# Moror_Driver_and_Power_Board_v2.net
KiCad netlist of a schematic drawn in EAGLE
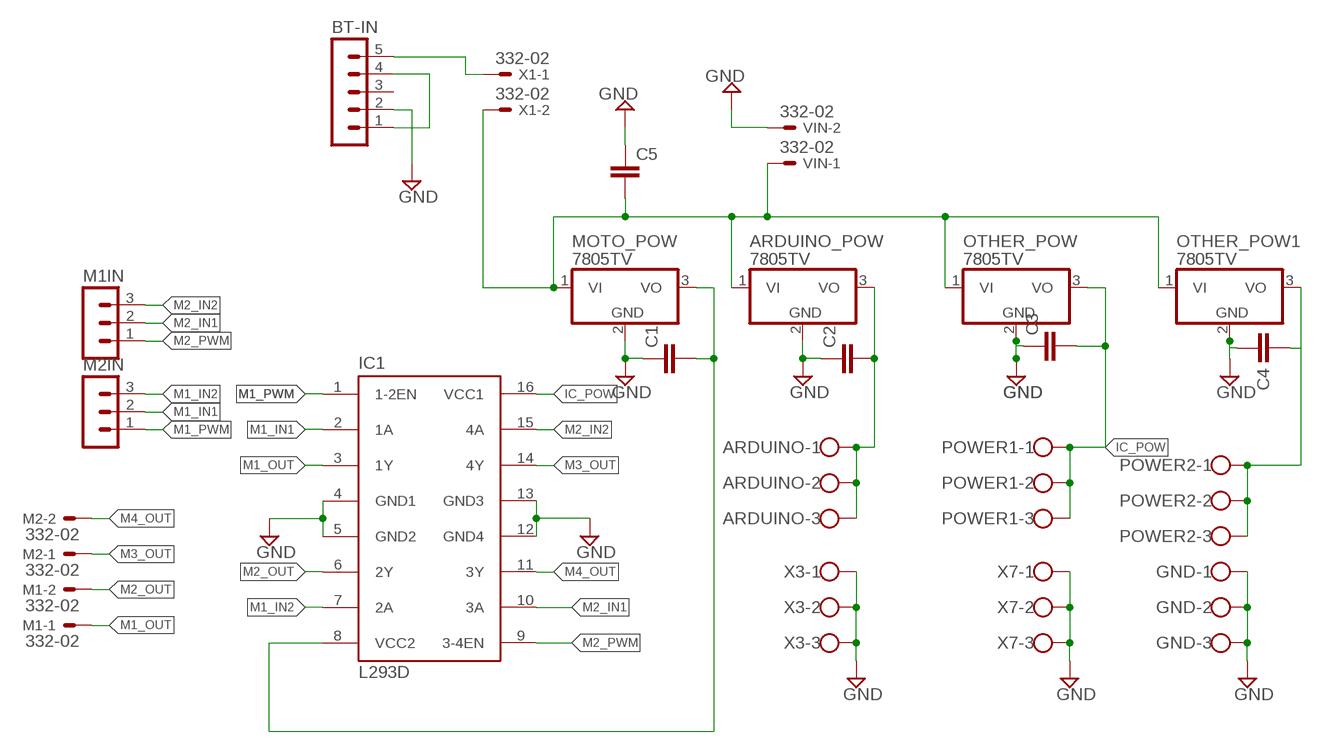
[diagram p0: schematic, sheet 1]

(export (version "E")
  (design (tool "Eeschema 10.0.6"))
  (components
    (comp (ref "ARDUINO")
      (value "W237-103")
      (footprint "eagle-import:W237-103")
      (fields (field (name "MPN") "237-103"))
      (libsource (lib "eagle-import") (part "W237-103"))
    )
    (comp (ref "ARDUINO_POW")
      (value "7805TV")
      (footprint "eagle-import:TO220V")
      (libsource (lib "eagle-import") (part "78TV05"))
    )
    (comp (ref "BT-IN")
      (value "MA05-1")
      (footprint "eagle-import:MA05-1")
      (libsource (lib "eagle-import") (part "MA05-1"))
    )
    (comp (ref "C1")
      (value "C-EU025-030X050")
      (footprint "eagle-import:C025-030X050")
      (libsource (lib "eagle-import") (part "C-EU025-030X050"))
    )
    (comp (ref "C2")
      (value "C-EU025-030X050")
      (footprint "eagle-import:C025-030X050")
      (libsource (lib "eagle-import") (part "C-EU025-030X050"))
    )
    (comp (ref "C3")
      (value "C-EU025-030X050")
      (footprint "eagle-import:C025-030X050")
      (libsource (lib "eagle-import") (part "C-EU025-030X050"))
    )
    (comp (ref "C4")
      (value "C-EU025-030X050")
      (footprint "eagle-import:C025-030X050")
      (libsource (lib "eagle-import") (part "C-EU025-030X050"))
    )
    (comp (ref "C5")
      (value "C-EU025-030X050")
      (footprint "eagle-import:C025-030X050")
      (libsource (lib "eagle-import") (part "C-EU025-030X050"))
    )
    (comp (ref "GND")
      (value "W237-103")
      (footprint "eagle-import:W237-103")
      (fields (field (name "MPN") "237-103"))
      (libsource (lib "eagle-import") (part "W237-103"))
    )
    (comp (ref "IC1")
      (value "L293D")
      (footprint "eagle-import:DIL16")
      (libsource (lib "eagle-import") (part "L293D"))
    )
    (comp (ref "M1")
      (value "332-02")
      (footprint "eagle-import:332-02")
      (libsource (lib "eagle-import") (part "332-02"))
    )
    (comp (ref "M1IN")
      (value "MA03-1")
      (footprint "eagle-import:MA03-1")
      (libsource (lib "eagle-import") (part "MA03-1"))
    )
    (comp (ref "M2")
      (value "332-02")
      (footprint "eagle-import:332-02")
      (libsource (lib "eagle-import") (part "332-02"))
    )
    (comp (ref "M2IN")
      (value "MA03-1")
      (footprint "eagle-import:MA03-1")
      (libsource (lib "eagle-import") (part "MA03-1"))
    )
    (comp (ref "MOTO_POW")
      (value "7805TV")
      (footprint "eagle-import:TO220V")
      (libsource (lib "eagle-import") (part "78TV05"))
    )
    (comp (ref "OTHER_POW")
      (value "7805TV")
      (footprint "eagle-import:TO220V")
      (libsource (lib "eagle-import") (part "78TV05"))
    )
    (comp (ref "OTHER_POW1")
      (value "7805TV")
      (footprint "eagle-import:TO220V")
      (libsource (lib "eagle-import") (part "78TV05"))
    )
    (comp (ref "POWER1")
      (value "W237-103")
      (footprint "eagle-import:W237-103")
      (fields (field (name "MPN") "237-103"))
      (libsource (lib "eagle-import") (part "W237-103"))
    )
    (comp (ref "POWER2")
      (value "W237-103")
      (footprint "eagle-import:W237-103")
      (fields (field (name "MPN") "237-103"))
      (libsource (lib "eagle-import") (part "W237-103"))
    )
    (comp (ref "VIN")
      (value "332-02")
      (footprint "eagle-import:332-02")
      (libsource (lib "eagle-import") (part "332-02"))
    )
    (comp (ref "X1")
      (value "332-02")
      (footprint "eagle-import:332-02")
      (libsource (lib "eagle-import") (part "332-02"))
    )
    (comp (ref "X3")
      (value "W237-103")
      (footprint "eagle-import:W237-103")
      (fields (field (name "MPN") "237-103"))
      (libsource (lib "eagle-import") (part "W237-103"))
    )
    (comp (ref "X7")
      (value "W237-103")
      (footprint "eagle-import:W237-103")
      (fields (field (name "MPN") "237-103"))
      (libsource (lib "eagle-import") (part "W237-103"))
    )
  )
  (nets
    (net (code "1") (name "GND") (class "Default")
      (node (ref "ARDUINO_POW") (pin "2") (pinfunction "GND_2") (pintype "passive"))
      (node (ref "BT-IN") (pin "2") (pinfunction "2_2") (pintype "passive"))
      (node (ref "C1") (pin "1") (pinfunction "1_1") (pintype "passive"))
      (node (ref "C2") (pin "1") (pinfunction "1_1") (pintype "passive"))
      (node (ref "C3") (pin "1") (pinfunction "1_1") (pintype "passive"))
      (node (ref "C4") (pin "1") (pinfunction "1_1") (pintype "passive"))
      (node (ref "C5") (pin "1") (pinfunction "1_1") (pintype "passive"))
      (node (ref "GND") (pin "1") (pinfunction "KL_1") (pintype "passive"))
      (node (ref "GND") (pin "2") (pinfunction "KL_2") (pintype "passive"))
      (node (ref "GND") (pin "3") (pinfunction "KL_3") (pintype "passive"))
      (node (ref "IC1") (pin "12") (pinfunction "GND4_12") (pintype "power_in"))
      (node (ref "IC1") (pin "13") (pinfunction "GND3_13") (pintype "power_in"))
      (node (ref "IC1") (pin "4") (pinfunction "GND1_4") (pintype "power_in"))
      (node (ref "IC1") (pin "5") (pinfunction "GND2_5") (pintype "power_in"))
      (node (ref "MOTO_POW") (pin "2") (pinfunction "GND_2") (pintype "passive"))
      (node (ref "OTHER_POW") (pin "2") (pinfunction "GND_2") (pintype "passive"))
      (node (ref "OTHER_POW1") (pin "2") (pinfunction "GND_2") (pintype "passive"))
      (node (ref "VIN") (pin "2") (pinfunction "S_2") (pintype "passive"))
      (node (ref "X3") (pin "1") (pinfunction "KL_1") (pintype "passive"))
      (node (ref "X3") (pin "2") (pinfunction "KL_2") (pintype "passive"))
      (node (ref "X3") (pin "3") (pinfunction "KL_3") (pintype "passive"))
      (node (ref "X7") (pin "1") (pinfunction "KL_1") (pintype "passive"))
      (node (ref "X7") (pin "2") (pinfunction "KL_2") (pintype "passive"))
      (node (ref "X7") (pin "3") (pinfunction "KL_3") (pintype "passive"))
    )
    (net (code "2") (name "IC_POW") (class "Default")
      (node (ref "C3") (pin "2") (pinfunction "2_2") (pintype "passive"))
      (node (ref "IC1") (pin "16") (pinfunction "VCC1_16") (pintype "power_in"))
      (node (ref "OTHER_POW") (pin "3") (pinfunction "VO_3") (pintype "passive"))
      (node (ref "POWER1") (pin "1") (pinfunction "KL_1") (pintype "passive"))
      (node (ref "POWER1") (pin "2") (pinfunction "KL_2") (pintype "passive"))
      (node (ref "POWER1") (pin "3") (pinfunction "KL_3") (pintype "passive"))
    )
    (net (code "3") (name "M1_IN1") (class "Default")
      (node (ref "IC1") (pin "2") (pinfunction "1A_2") (pintype "input"))
      (node (ref "M2IN") (pin "2") (pinfunction "2_2") (pintype "passive"))
    )
    (net (code "4") (name "M1_IN2") (class "Default")
      (node (ref "IC1") (pin "7") (pinfunction "2A_7") (pintype "input"))
      (node (ref "M2IN") (pin "3") (pinfunction "3_3") (pintype "passive"))
    )
    (net (code "5") (name "M1_OUT") (class "Default")
      (node (ref "IC1") (pin "3") (pinfunction "1Y_3") (pintype "output"))
      (node (ref "M1") (pin "1") (pinfunction "S_1") (pintype "passive"))
    )
    (net (code "6") (name "M1_PWM") (class "Default")
      (node (ref "IC1") (pin "1") (pinfunction "1-2EN_1") (pintype "input"))
      (node (ref "M2IN") (pin "1") (pinfunction "1_1") (pintype "passive"))
    )
    (net (code "7") (name "M2_IN1") (class "Default")
      (node (ref "IC1") (pin "10") (pinfunction "3A_10") (pintype "input"))
      (node (ref "M1IN") (pin "2") (pinfunction "2_2") (pintype "passive"))
    )
    (net (code "8") (name "M2_IN2") (class "Default")
      (node (ref "IC1") (pin "15") (pinfunction "4A_15") (pintype "input"))
      (node (ref "M1IN") (pin "3") (pinfunction "3_3") (pintype "passive"))
    )
    (net (code "9") (name "M2_OUT") (class "Default")
      (node (ref "IC1") (pin "6") (pinfunction "2Y_6") (pintype "output"))
      (node (ref "M1") (pin "2") (pinfunction "S_2") (pintype "passive"))
    )
    (net (code "10") (name "M2_PWM") (class "Default")
      (node (ref "IC1") (pin "9") (pinfunction "3-4EN_9") (pintype "input"))
      (node (ref "M1IN") (pin "1") (pinfunction "1_1") (pintype "passive"))
    )
    (net (code "11") (name "M3_OUT") (class "Default")
      (node (ref "IC1") (pin "14") (pinfunction "4Y_14") (pintype "output"))
      (node (ref "M2") (pin "1") (pinfunction "S_1") (pintype "passive"))
    )
    (net (code "12") (name "M4_OUT") (class "Default")
      (node (ref "IC1") (pin "11") (pinfunction "3Y_11") (pintype "output"))
      (node (ref "M2") (pin "2") (pinfunction "S_2") (pintype "passive"))
    )
    (net (code "13") (name "Net-(ARDUINOA-KL)") (class "Default")
      (node (ref "ARDUINO") (pin "1") (pinfunction "KL_1") (pintype "passive"))
      (node (ref "ARDUINO") (pin "2") (pinfunction "KL_2") (pintype "passive"))
      (node (ref "ARDUINO") (pin "3") (pinfunction "KL_3") (pintype "passive"))
      (node (ref "ARDUINO_POW") (pin "3") (pinfunction "VO_3") (pintype "passive"))
      (node (ref "C2") (pin "2") (pinfunction "2_2") (pintype "passive"))
    )
    (net (code "14") (name "Net-(ARDUINO_POW-VI)") (class "Default")
      (node (ref "ARDUINO_POW") (pin "1") (pinfunction "VI_1") (pintype "input"))
      (node (ref "C5") (pin "2") (pinfunction "2_2") (pintype "passive"))
      (node (ref "MOTO_POW") (pin "1") (pinfunction "VI_1") (pintype "input"))
      (node (ref "OTHER_POW") (pin "1") (pinfunction "VI_1") (pintype "input"))
      (node (ref "OTHER_POW1") (pin "1") (pinfunction "VI_1") (pintype "input"))
      (node (ref "VIN") (pin "1") (pinfunction "S_1") (pintype "passive"))
      (node (ref "X1") (pin "2") (pinfunction "S_2") (pintype "passive"))
    )
    (net (code "15") (name "Net-(BT-IN-Pad1)") (class "Default")
      (node (ref "BT-IN") (pin "1") (pinfunction "1_1") (pintype "passive"))
      (node (ref "BT-IN") (pin "4") (pinfunction "4_4") (pintype "passive"))
    )
    (net (code "16") (name "Net-(IC1-VCC2)") (class "Default")
      (node (ref "C1") (pin "2") (pinfunction "2_2") (pintype "passive"))
      (node (ref "IC1") (pin "8") (pinfunction "VCC2_8") (pintype "power_in"))
      (node (ref "MOTO_POW") (pin "3") (pinfunction "VO_3") (pintype "passive"))
    )
    (net (code "17") (name "Net-(OTHER_POW1-VO)") (class "Default")
      (node (ref "C4") (pin "2") (pinfunction "2_2") (pintype "passive"))
      (node (ref "OTHER_POW1") (pin "3") (pinfunction "VO_3") (pintype "passive"))
      (node (ref "POWER2") (pin "1") (pinfunction "KL_1") (pintype "passive"))
      (node (ref "POWER2") (pin "2") (pinfunction "KL_2") (pintype "passive"))
      (node (ref "POWER2") (pin "3") (pinfunction "KL_3") (pintype "passive"))
    )
    (net (code "18") (name "Net-(X1A-S)") (class "Default")
      (node (ref "BT-IN") (pin "5") (pinfunction "5_5") (pintype "passive"))
      (node (ref "X1") (pin "1") (pinfunction "S_1") (pintype "passive"))
    )
    (net (code "19") (name "unconnected-(BT-IN-Pad3)") (class "Default")
      (node (ref "BT-IN") (pin "3") (pinfunction "3_3") (pintype "passive"))
    )
  )
)
